# MyProSch3.net
KiCad netlist of a schematic drawn in Altium Designer
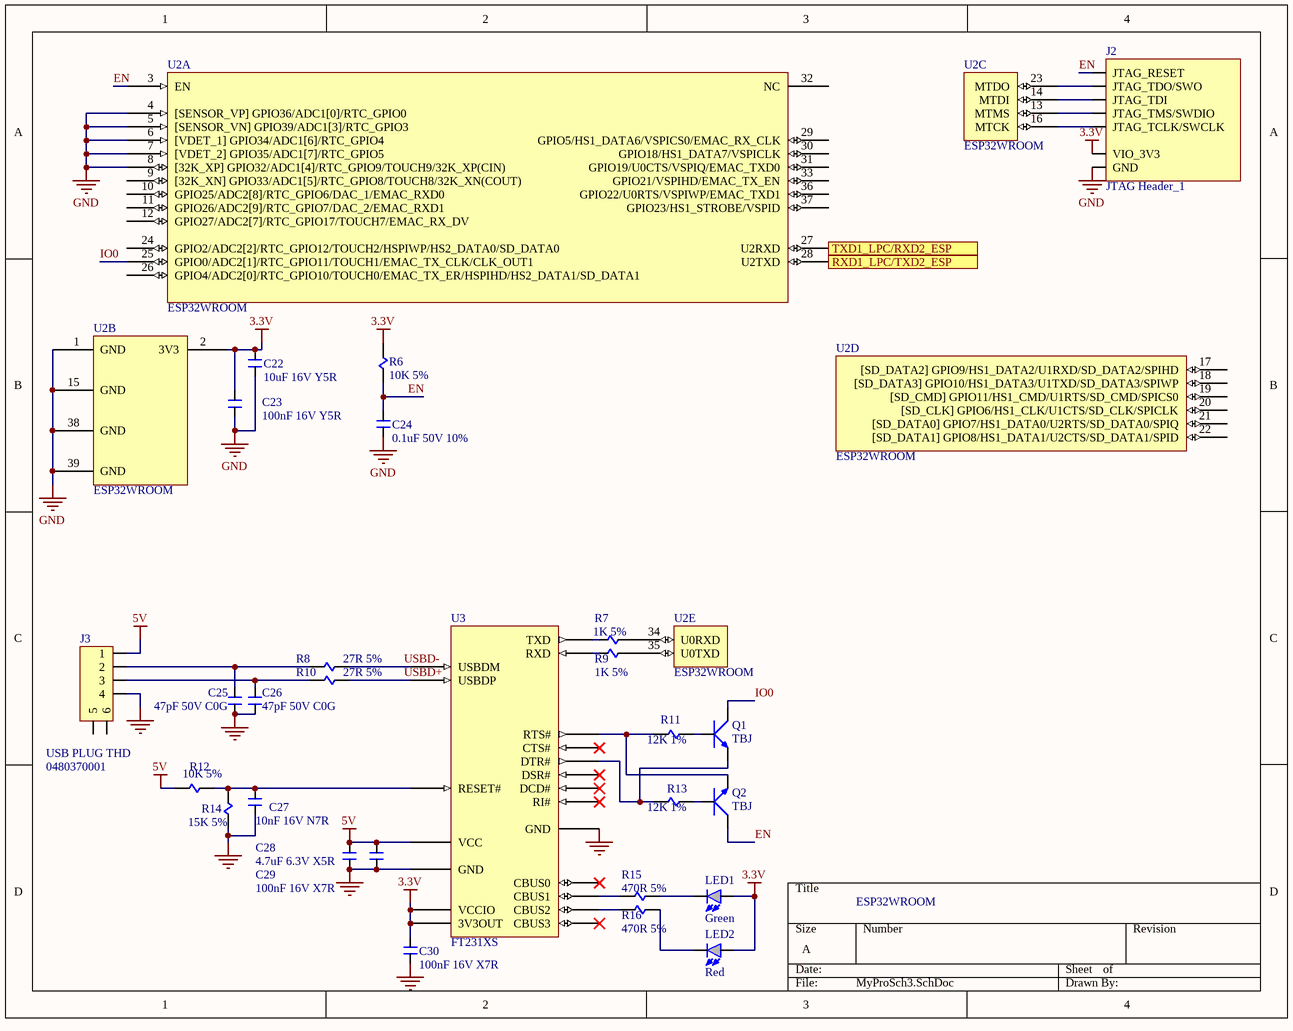
[diagram p0: MyProSch3.SchDoc]

(export (version "E")
  (design (tool "Eeschema 10.0.6"))
  (components
    (comp (ref "C22")
      (value "10uF 16V Y5R")
      (footprint "C_0805")
      (description "Capacitor")
      (libsource (lib "MyPro") (part "Capacitor"))
    )
    (comp (ref "C23")
      (value "100nF 16V Y5R")
      (footprint "C_0805")
      (description "Capacitor")
      (libsource (lib "MyPro") (part "Capacitor"))
    )
    (comp (ref "C24")
      (value "0.1uF 50V 10%")
      (footprint "C_0805")
      (description "Capacitor")
      (libsource (lib "MyPro") (part "Capacitor"))
    )
    (comp (ref "C25")
      (value "47pF 50V C0G")
      (footprint "C_0805")
      (description "Capacitor")
      (libsource (lib "BridgeUSB") (part "Capacitor"))
    )
    (comp (ref "C26")
      (value "47pF 50V C0G")
      (footprint "C_0805")
      (description "Capacitor")
      (libsource (lib "BridgeUSB") (part "Capacitor"))
    )
    (comp (ref "C27")
      (value "10nF 16V N7R")
      (footprint "C_0805")
      (description "Capacitor")
      (libsource (lib "BridgeUSB") (part "Capacitor"))
    )
    (comp (ref "C28")
      (value "4.7uF 6.3V X5R")
      (footprint "C_0805")
      (description "Capacitor")
      (libsource (lib "BridgeUSB") (part "Capacitor"))
    )
    (comp (ref "C29")
      (value "100nF 16V X7R")
      (footprint "C_0805")
      (description "Capacitor")
      (libsource (lib "BridgeUSB") (part "Capacitor"))
    )
    (comp (ref "C30")
      (value "100nF 16V X7R")
      (footprint "C_0805")
      (description "Capacitor")
      (libsource (lib "BridgeUSB") (part "Capacitor"))
    )
    (comp (ref "J2")
      (value "JTAG Header_1")
      (footprint "HDRM_2.54mm_1X8")
      (libsource (lib "MyPro") (part "JTAG Header_1"))
    )
    (comp (ref "J3")
      (value "USB PLUG THD")
      (footprint "USB_HDRM_A")
      (fields (field (name "PARAMETER 1") "0480370001"))
      (libsource (lib "BridgeUSB") (part "Connectorx6"))
    )
    (comp (ref "LED1")
      (value "Green")
      (footprint "Led_0805")
      (description "Green LED")
      (libsource (lib "MyPro") (part "Led_G"))
    )
    (comp (ref "LED2")
      (value "Red")
      (footprint "Led_0805")
      (description "Red LED")
      (libsource (lib "MyPro") (part "Led_R"))
    )
    (comp (ref "Q1") (value "TBJ") (footprint "SOT-23") (libsource (lib "MyPro") (part "TBJ_NPN")))
    (comp (ref "Q2") (value "TBJ") (footprint "SOT-23") (libsource (lib "MyPro") (part "TBJ_NPN")))
    (comp (ref "R6")
      (value "10K 5%")
      (footprint "R_0805")
      (description "Resistor")
      (libsource (lib "MyPro") (part "Resistor"))
    )
    (comp (ref "R7")
      (value "1K 5%")
      (footprint "R_0805")
      (description "Resistor")
      (libsource (lib "BridgeUSB") (part "Resistor"))
    )
    (comp (ref "R8")
      (value "27R 5%")
      (footprint "R_0805")
      (description "Resistor")
      (libsource (lib "BridgeUSB") (part "Resistor"))
    )
    (comp (ref "R9")
      (value "1K 5%")
      (footprint "R_0805")
      (description "Resistor")
      (libsource (lib "BridgeUSB") (part "Resistor"))
    )
    (comp (ref "R10")
      (value "27R 5%")
      (footprint "R_0805")
      (description "Resistor")
      (libsource (lib "BridgeUSB") (part "Resistor"))
    )
    (comp (ref "R11")
      (value "12K 1%")
      (footprint "R_0805")
      (description "Resistor")
      (libsource (lib "MyPro") (part "Resistor"))
    )
    (comp (ref "R12")
      (value "10K 5%")
      (footprint "R_0805")
      (description "Resistor")
      (libsource (lib "BridgeUSB") (part "Resistor"))
    )
    (comp (ref "R13")
      (value "12K 1%")
      (footprint "R_0805")
      (description "Resistor")
      (libsource (lib "MyPro") (part "Resistor"))
    )
    (comp (ref "R14")
      (value "15K 5%")
      (footprint "R_0805")
      (description "Resistor")
      (libsource (lib "BridgeUSB") (part "Resistor"))
    )
    (comp (ref "R15")
      (value "470R 5%")
      (footprint "R_0805")
      (description "Resistor")
      (libsource (lib "BridgeUSB") (part "Resistor"))
    )
    (comp (ref "R16")
      (value "470R 5%")
      (footprint "R_0805")
      (description "Resistor")
      (libsource (lib "BridgeUSB") (part "Resistor"))
    )
    (comp (ref "U2")
      (value "ESP32WROOM")
      (footprint "ESP32_WROOM - duplicate")
      (libsource (lib "MyPro") (part "ESP32WROOM"))
    )
    (comp (ref "U3") (value "FT231XS") (footprint "SSOP_20") (libsource (lib "MyPro") (part "FT231XS")))
  )
  (nets
    (net (code "1") (name "/EN") (class "Default")
      (node (ref "C24") (pin "1") (pinfunction "A1_1") (pintype "passive"))
      (node (ref "J2") (pin "4") (pinfunction "JTAG_RESET_4") (pintype "passive"))
      (node (ref "Q2") (pin "3") (pinfunction "C_3") (pintype "passive"))
      (node (ref "R6") (pin "1") (pinfunction "P1_1") (pintype "passive"))
      (node (ref "U2") (pin "3") (pinfunction "EN_3") (pintype "input"))
    )
    (net (code "2") (name "/IO0") (class "Default")
      (node (ref "Q1") (pin "3") (pinfunction "C_3") (pintype "passive"))
      (node (ref "U2") (pin "25") (pinfunction "GPIO0/ADC2[1]/RTC_GPIO11/TOUCH1/EMAC_TX_CLK/CLK_OUT1_25") (pintype "bidirectional"))
    )
    (net (code "3") (name "/RXD1_LPC{slash}TXD2_ESP") (class "Default")
      (node (ref "U2") (pin "28") (pinfunction "U2TXD_28") (pintype "bidirectional"))
    )
    (net (code "4") (name "/TXD1_LPC{slash}RXD2_ESP") (class "Default")
      (node (ref "U2") (pin "27") (pinfunction "U2RXD_27") (pintype "bidirectional"))
    )
    (net (code "5") (name "/USBD+") (class "Default")
      (node (ref "R10") (pin "2") (pinfunction "P2_2") (pintype "passive"))
      (node (ref "U3") (pin "11") (pinfunction "USBDP_11") (pintype "input"))
    )
    (net (code "6") (name "/USBD-") (class "Default")
      (node (ref "R8") (pin "2") (pinfunction "P2_2") (pintype "passive"))
      (node (ref "U3") (pin "12") (pinfunction "USBDM_12") (pintype "input"))
    )
    (net (code "7") (name "3.3V") (class "Default")
      (node (ref "C22") (pin "1") (pinfunction "A1_1") (pintype "passive"))
      (node (ref "C23") (pin "1") (pinfunction "A1_1") (pintype "passive"))
      (node (ref "C30") (pin "1") (pinfunction "A1_1") (pintype "passive"))
      (node (ref "J2") (pin "1") (pinfunction "VIO_3V3_1") (pintype "passive"))
      (node (ref "LED1") (pin "1") (pinfunction "A_1") (pintype "passive"))
      (node (ref "LED2") (pin "1") (pinfunction "A_1") (pintype "passive"))
      (node (ref "R6") (pin "2") (pinfunction "P2_2") (pintype "passive"))
      (node (ref "U2") (pin "2") (pinfunction "3V3_2") (pintype "passive"))
      (node (ref "U3") (pin "13") (pinfunction "3V3OUT_13") (pintype "power_in"))
      (node (ref "U3") (pin "3") (pinfunction "VCCIO_3") (pintype "power_in"))
    )
    (net (code "8") (name "5V") (class "Default")
      (node (ref "C28") (pin "1") (pinfunction "A1_1") (pintype "passive"))
      (node (ref "C29") (pin "1") (pinfunction "A1_1") (pintype "passive"))
      (node (ref "J3") (pin "1") (pinfunction "1_1") (pintype "passive"))
      (node (ref "R12") (pin "1") (pinfunction "P1_1") (pintype "passive"))
      (node (ref "U3") (pin "15") (pinfunction "VCC_15") (pintype "power_in"))
    )
    (net (code "9") (name "GND") (class "Default")
      (node (ref "C22") (pin "2") (pinfunction "A2_2") (pintype "passive"))
      (node (ref "C23") (pin "2") (pinfunction "A2_2") (pintype "passive"))
      (node (ref "C24") (pin "2") (pinfunction "A2_2") (pintype "passive"))
      (node (ref "C25") (pin "2") (pinfunction "A2_2") (pintype "passive"))
      (node (ref "C26") (pin "2") (pinfunction "A2_2") (pintype "passive"))
      (node (ref "C27") (pin "2") (pinfunction "A2_2") (pintype "passive"))
      (node (ref "C28") (pin "2") (pinfunction "A2_2") (pintype "passive"))
      (node (ref "C29") (pin "2") (pinfunction "A2_2") (pintype "passive"))
      (node (ref "C30") (pin "2") (pinfunction "A2_2") (pintype "passive"))
      (node (ref "J2") (pin "3") (pinfunction "GND_3") (pintype "passive"))
      (node (ref "J3") (pin "4") (pinfunction "4_4") (pintype "passive"))
      (node (ref "R14") (pin "2") (pinfunction "P2_2") (pintype "passive"))
      (node (ref "U2") (pin "1") (pinfunction "GND_1") (pintype "passive"))
      (node (ref "U2") (pin "15") (pinfunction "GND_15") (pintype "passive"))
      (node (ref "U2") (pin "38") (pinfunction "GND_38") (pintype "passive"))
      (node (ref "U2") (pin "39") (pinfunction "GND_39") (pintype "passive"))
      (node (ref "U2") (pin "4") (pinfunction "[SENSOR_VP]_GPIO36/ADC1[0]/RTC_GPIO0_4") (pintype "input"))
      (node (ref "U2") (pin "5") (pinfunction "[SENSOR_VN]_GPIO39/ADC1[3]/RTC_GPIO3_5") (pintype "input"))
      (node (ref "U2") (pin "6") (pinfunction "[VDET_1]_GPIO34/ADC1[6]/RTC_GPIO4_6") (pintype "input"))
      (node (ref "U2") (pin "7") (pinfunction "[VDET_2]_GPIO35/ADC1[7]/RTC_GPIO5_7") (pintype "input"))
      (node (ref "U2") (pin "8") (pinfunction "[32K_XP]_GPIO32/ADC1[4]/RTC_GPIO9/TOUCH9/32K_XP(CIN)_8") (pintype "bidirectional"))
      (node (ref "U3") (pin "16") (pinfunction "GND_16") (pintype "power_in"))
      (node (ref "U3") (pin "6") (pinfunction "GND_6") (pintype "power_in"))
    )
    (net (code "10") (name "Net-(C25-A1)") (class "Default")
      (node (ref "C25") (pin "1") (pinfunction "A1_1") (pintype "passive"))
      (node (ref "J3") (pin "2") (pinfunction "2_2") (pintype "passive"))
      (node (ref "R8") (pin "1") (pinfunction "P1_1") (pintype "passive"))
    )
    (net (code "11") (name "Net-(C26-A1)") (class "Default")
      (node (ref "C26") (pin "1") (pinfunction "A1_1") (pintype "passive"))
      (node (ref "J3") (pin "3") (pinfunction "3_3") (pintype "passive"))
      (node (ref "R10") (pin "1") (pinfunction "P1_1") (pintype "passive"))
    )
    (net (code "12") (name "Net-(C27-A1)") (class "Default")
      (node (ref "C27") (pin "1") (pinfunction "A1_1") (pintype "passive"))
      (node (ref "R12") (pin "2") (pinfunction "P2_2") (pintype "passive"))
      (node (ref "R14") (pin "1") (pinfunction "P1_1") (pintype "passive"))
      (node (ref "U3") (pin "14") (pinfunction "RESET#_14") (pintype "input"))
    )
    (net (code "13") (name "Net-(J2-JTAG_TCLK{slash}SWCLK)") (class "Default")
      (node (ref "J2") (pin "7") (pinfunction "JTAG_TCLK/SWCLK_7") (pintype "passive"))
      (node (ref "U2") (pin "16") (pinfunction "MTCK_16") (pintype "bidirectional"))
    )
    (net (code "14") (name "Net-(J2-JTAG_TDI)") (class "Default")
      (node (ref "J2") (pin "6") (pinfunction "JTAG_TDI_6") (pintype "passive"))
      (node (ref "U2") (pin "14") (pinfunction "MTDI_14") (pintype "bidirectional"))
    )
    (net (code "15") (name "Net-(J2-JTAG_TDO{slash}SWO)") (class "Default")
      (node (ref "J2") (pin "8") (pinfunction "JTAG_TDO/SWO_8") (pintype "passive"))
      (node (ref "U2") (pin "23") (pinfunction "MTDO_23") (pintype "bidirectional"))
    )
    (net (code "16") (name "Net-(J2-JTAG_TMS{slash}SWDIO)") (class "Default")
      (node (ref "J2") (pin "5") (pinfunction "JTAG_TMS/SWDIO_5") (pintype "passive"))
      (node (ref "U2") (pin "13") (pinfunction "MTMS_13") (pintype "bidirectional"))
    )
    (net (code "17") (name "Net-(LED1-K)") (class "Default")
      (node (ref "LED1") (pin "2") (pinfunction "K_2") (pintype "passive"))
      (node (ref "R15") (pin "2") (pinfunction "P2_2") (pintype "passive"))
    )
    (net (code "18") (name "Net-(LED2-K)") (class "Default")
      (node (ref "LED2") (pin "2") (pinfunction "K_2") (pintype "passive"))
      (node (ref "R16") (pin "2") (pinfunction "P2_2") (pintype "passive"))
    )
    (net (code "19") (name "Net-(Q1-B)") (class "Default")
      (node (ref "Q1") (pin "1") (pinfunction "B_1") (pintype "passive"))
      (node (ref "R11") (pin "2") (pinfunction "P2_2") (pintype "passive"))
    )
    (net (code "20") (name "Net-(Q1-E)") (class "Default")
      (node (ref "Q1") (pin "2") (pinfunction "E_2") (pintype "passive"))
      (node (ref "R13") (pin "1") (pinfunction "P1_1") (pintype "passive"))
      (node (ref "U3") (pin "1") (pinfunction "DTR#_1") (pintype "output"))
    )
    (net (code "21") (name "Net-(Q2-B)") (class "Default")
      (node (ref "Q2") (pin "1") (pinfunction "B_1") (pintype "passive"))
      (node (ref "R13") (pin "2") (pinfunction "P2_2") (pintype "passive"))
    )
    (net (code "22") (name "Net-(Q2-E)") (class "Default")
      (node (ref "Q2") (pin "2") (pinfunction "E_2") (pintype "passive"))
      (node (ref "R11") (pin "1") (pinfunction "P1_1") (pintype "passive"))
      (node (ref "U3") (pin "2") (pinfunction "RTS#_2") (pintype "output"))
    )
    (net (code "23") (name "Net-(R7-P1)") (class "Default")
      (node (ref "R7") (pin "1") (pinfunction "P1_1") (pintype "passive"))
      (node (ref "U3") (pin "20") (pinfunction "TXD_20") (pintype "output"))
    )
    (net (code "24") (name "Net-(R7-P2)") (class "Default")
      (node (ref "R7") (pin "2") (pinfunction "P2_2") (pintype "passive"))
      (node (ref "U2") (pin "34") (pinfunction "U0RXD_34") (pintype "bidirectional"))
    )
    (net (code "25") (name "Net-(R9-P1)") (class "Default")
      (node (ref "R9") (pin "1") (pinfunction "P1_1") (pintype "passive"))
      (node (ref "U3") (pin "4") (pinfunction "RXD_4") (pintype "input"))
    )
    (net (code "26") (name "Net-(R9-P2)") (class "Default")
      (node (ref "R9") (pin "2") (pinfunction "P2_2") (pintype "passive"))
      (node (ref "U2") (pin "35") (pinfunction "U0TXD_35") (pintype "bidirectional"))
    )
    (net (code "27") (name "Net-(R15-P1)") (class "Default")
      (node (ref "R15") (pin "1") (pinfunction "P1_1") (pintype "passive"))
      (node (ref "U3") (pin "17") (pinfunction "CBUS1_17") (pintype "bidirectional"))
    )
    (net (code "28") (name "Net-(R16-P1)") (class "Default")
      (node (ref "R16") (pin "1") (pinfunction "P1_1") (pintype "passive"))
      (node (ref "U3") (pin "10") (pinfunction "CBUS2_10") (pintype "bidirectional"))
    )
    (net (code "29") (name "unconnected-(J3-Pad5)") (class "Default")
      (node (ref "J3") (pin "5") (pinfunction "5_5") (pintype "passive"))
    )
    (net (code "30") (name "unconnected-(J3-Pad6)") (class "Default")
      (node (ref "J3") (pin "6") (pinfunction "6_6") (pintype "passive"))
    )
    (net (code "31") (name "unconnected-(U2A-GPIO2{slash}ADC2[2]{slash}RTC_GPIO12{slash}TOUCH2{slash}HSPIWP{slash}HS2_DATA0{slash}SD_DATA0-Pad24)") (class "Default")
      (node (ref "U2") (pin "24") (pinfunction "GPIO2/ADC2[2]/RTC_GPIO12/TOUCH2/HSPIWP/HS2_DATA0/SD_DATA0_24") (pintype "bidirectional"))
    )
    (net (code "32") (name "unconnected-(U2A-GPIO4{slash}ADC2[0]{slash}RTC_GPIO10{slash}TOUCH0{slash}EMAC_TX_ER{slash}HSPIHD{slash}HS2_DATA1{slash}SD_DATA1-Pad26)") (class "Default")
      (node (ref "U2") (pin "26") (pinfunction "GPIO4/ADC2[0]/RTC_GPIO10/TOUCH0/EMAC_TX_ER/HSPIHD/HS2_DATA1/SD_DATA1_26") (pintype "bidirectional"))
    )
    (net (code "33") (name "unconnected-(U2A-GPIO5{slash}HS1_DATA6{slash}VSPICS0{slash}EMAC_RX_CLK-Pad29)") (class "Default")
      (node (ref "U2") (pin "29") (pinfunction "GPIO5/HS1_DATA6/VSPICS0/EMAC_RX_CLK_29") (pintype "bidirectional"))
    )
    (net (code "34") (name "unconnected-(U2A-GPIO18{slash}HS1_DATA7{slash}VSPICLK-Pad30)") (class "Default")
      (node (ref "U2") (pin "30") (pinfunction "GPIO18/HS1_DATA7/VSPICLK_30") (pintype "bidirectional"))
    )
    (net (code "35") (name "unconnected-(U2A-GPIO19{slash}U0CTS{slash}VSPIQ{slash}EMAC_TXD0-Pad31)") (class "Default")
      (node (ref "U2") (pin "31") (pinfunction "GPIO19/U0CTS/VSPIQ/EMAC_TXD0_31") (pintype "bidirectional"))
    )
    (net (code "36") (name "unconnected-(U2A-GPIO21{slash}VSPIHD{slash}EMAC_TX_EN-Pad33)") (class "Default")
      (node (ref "U2") (pin "33") (pinfunction "GPIO21/VSPIHD/EMAC_TX_EN_33") (pintype "bidirectional"))
    )
    (net (code "37") (name "unconnected-(U2A-GPIO22{slash}U0RTS{slash}VSPIWP{slash}EMAC_TXD1-Pad36)") (class "Default")
      (node (ref "U2") (pin "36") (pinfunction "GPIO22/U0RTS/VSPIWP/EMAC_TXD1_36") (pintype "bidirectional"))
    )
    (net (code "38") (name "unconnected-(U2A-GPIO23{slash}HS1_STROBE{slash}VSPID-Pad37)") (class "Default")
      (node (ref "U2") (pin "37") (pinfunction "GPIO23/HS1_STROBE/VSPID_37") (pintype "bidirectional"))
    )
    (net (code "39") (name "unconnected-(U2A-GPIO25{slash}ADC2[8]{slash}RTC_GPIO6{slash}DAC_1{slash}EMAC_RXD0-Pad10)") (class "Default")
      (node (ref "U2") (pin "10") (pinfunction "GPIO25/ADC2[8]/RTC_GPIO6/DAC_1/EMAC_RXD0_10") (pintype "bidirectional"))
    )
    (net (code "40") (name "unconnected-(U2A-GPIO26{slash}ADC2[9]{slash}RTC_GPIO7{slash}DAC_2{slash}EMAC_RXD1-Pad11)") (class "Default")
      (node (ref "U2") (pin "11") (pinfunction "GPIO26/ADC2[9]/RTC_GPIO7/DAC_2/EMAC_RXD1_11") (pintype "bidirectional"))
    )
    (net (code "41") (name "unconnected-(U2A-GPIO27{slash}ADC2[7]{slash}RTC_GPIO17{slash}TOUCH7{slash}EMAC_RX_DV-Pad12)") (class "Default")
      (node (ref "U2") (pin "12") (pinfunction "GPIO27/ADC2[7]/RTC_GPIO17/TOUCH7/EMAC_RX_DV_12") (pintype "bidirectional"))
    )
    (net (code "42") (name "unconnected-(U2A-NC-Pad32)") (class "Default")
      (node (ref "U2") (pin "32") (pinfunction "NC_32") (pintype "passive"))
    )
    (net (code "43") (name "unconnected-(U2A-[32K_XN]_GPIO33{slash}ADC1[5]{slash}RTC_GPIO8{slash}TOUCH8{slash}32K_XN(COUT)-Pad9)") (class "Default")
      (node (ref "U2") (pin "9") (pinfunction "[32K_XN]_GPIO33/ADC1[5]/RTC_GPIO8/TOUCH8/32K_XN(COUT)_9") (pintype "bidirectional"))
    )
    (net (code "44") (name "unconnected-(U2D-[SD_CLK]_GPIO6{slash}HS1_CLK{slash}U1CTS{slash}SD_CLK{slash}SPICLK-Pad20)") (class "Default")
      (node (ref "U2") (pin "20") (pinfunction "[SD_CLK]_GPIO6/HS1_CLK/U1CTS/SD_CLK/SPICLK_20") (pintype "bidirectional"))
    )
    (net (code "45") (name "unconnected-(U2D-[SD_CMD]_GPIO11{slash}HS1_CMD{slash}U1RTS{slash}SD_CMD{slash}SPICS0-Pad19)") (class "Default")
      (node (ref "U2") (pin "19") (pinfunction "[SD_CMD]_GPIO11/HS1_CMD/U1RTS/SD_CMD/SPICS0_19") (pintype "bidirectional"))
    )
    (net (code "46") (name "unconnected-(U2D-[SD_DATA0]_GPIO7{slash}HS1_DATA0{slash}U2RTS{slash}SD_DATA0{slash}SPIQ-Pad21)") (class "Default")
      (node (ref "U2") (pin "21") (pinfunction "[SD_DATA0]_GPIO7/HS1_DATA0/U2RTS/SD_DATA0/SPIQ_21") (pintype "bidirectional"))
    )
    (net (code "47") (name "unconnected-(U2D-[SD_DATA1]_GPIO8{slash}HS1_DATA1{slash}U2CTS{slash}SD_DATA1{slash}SPID-Pad22)") (class "Default")
      (node (ref "U2") (pin "22") (pinfunction "[SD_DATA1]_GPIO8/HS1_DATA1/U2CTS/SD_DATA1/SPID_22") (pintype "bidirectional"))
    )
    (net (code "48") (name "unconnected-(U2D-[SD_DATA2]_GPIO9{slash}HS1_DATA2{slash}U1RXD{slash}SD_DATA2{slash}SPIHD-Pad17)") (class "Default")
      (node (ref "U2") (pin "17") (pinfunction "[SD_DATA2]_GPIO9/HS1_DATA2/U1RXD/SD_DATA2/SPIHD_17") (pintype "bidirectional"))
    )
    (net (code "49") (name "unconnected-(U2D-[SD_DATA3]_GPIO10{slash}HS1_DATA3{slash}U1TXD{slash}SD_DATA3{slash}SPIWP-Pad18)") (class "Default")
      (node (ref "U2") (pin "18") (pinfunction "[SD_DATA3]_GPIO10/HS1_DATA3/U1TXD/SD_DATA3/SPIWP_18") (pintype "bidirectional"))
    )
    (net (code "50") (name "unconnected-(U3-CBUS0-Pad18)") (class "Default")
      (node (ref "U3") (pin "18") (pinfunction "CBUS0_18") (pintype "bidirectional+no_connect"))
    )
    (net (code "51") (name "unconnected-(U3-CBUS3-Pad19)") (class "Default")
      (node (ref "U3") (pin "19") (pinfunction "CBUS3_19") (pintype "bidirectional+no_connect"))
    )
    (net (code "52") (name "unconnected-(U3-CTS#-Pad9)") (class "Default")
      (node (ref "U3") (pin "9") (pinfunction "CTS#_9") (pintype "input+no_connect"))
    )
    (net (code "53") (name "unconnected-(U3-DCD#-Pad8)") (class "Default")
      (node (ref "U3") (pin "8") (pinfunction "DCD#_8") (pintype "input+no_connect"))
    )
    (net (code "54") (name "unconnected-(U3-DSR#-Pad7)") (class "Default")
      (node (ref "U3") (pin "7") (pinfunction "DSR#_7") (pintype "input+no_connect"))
    )
    (net (code "55") (name "unconnected-(U3-RI#-Pad5)") (class "Default")
      (node (ref "U3") (pin "5") (pinfunction "RI#_5") (pintype "input+no_connect"))
    )
  )
)
